# connectors.net
KiCad netlist of a schematic drawn in Altium Designer
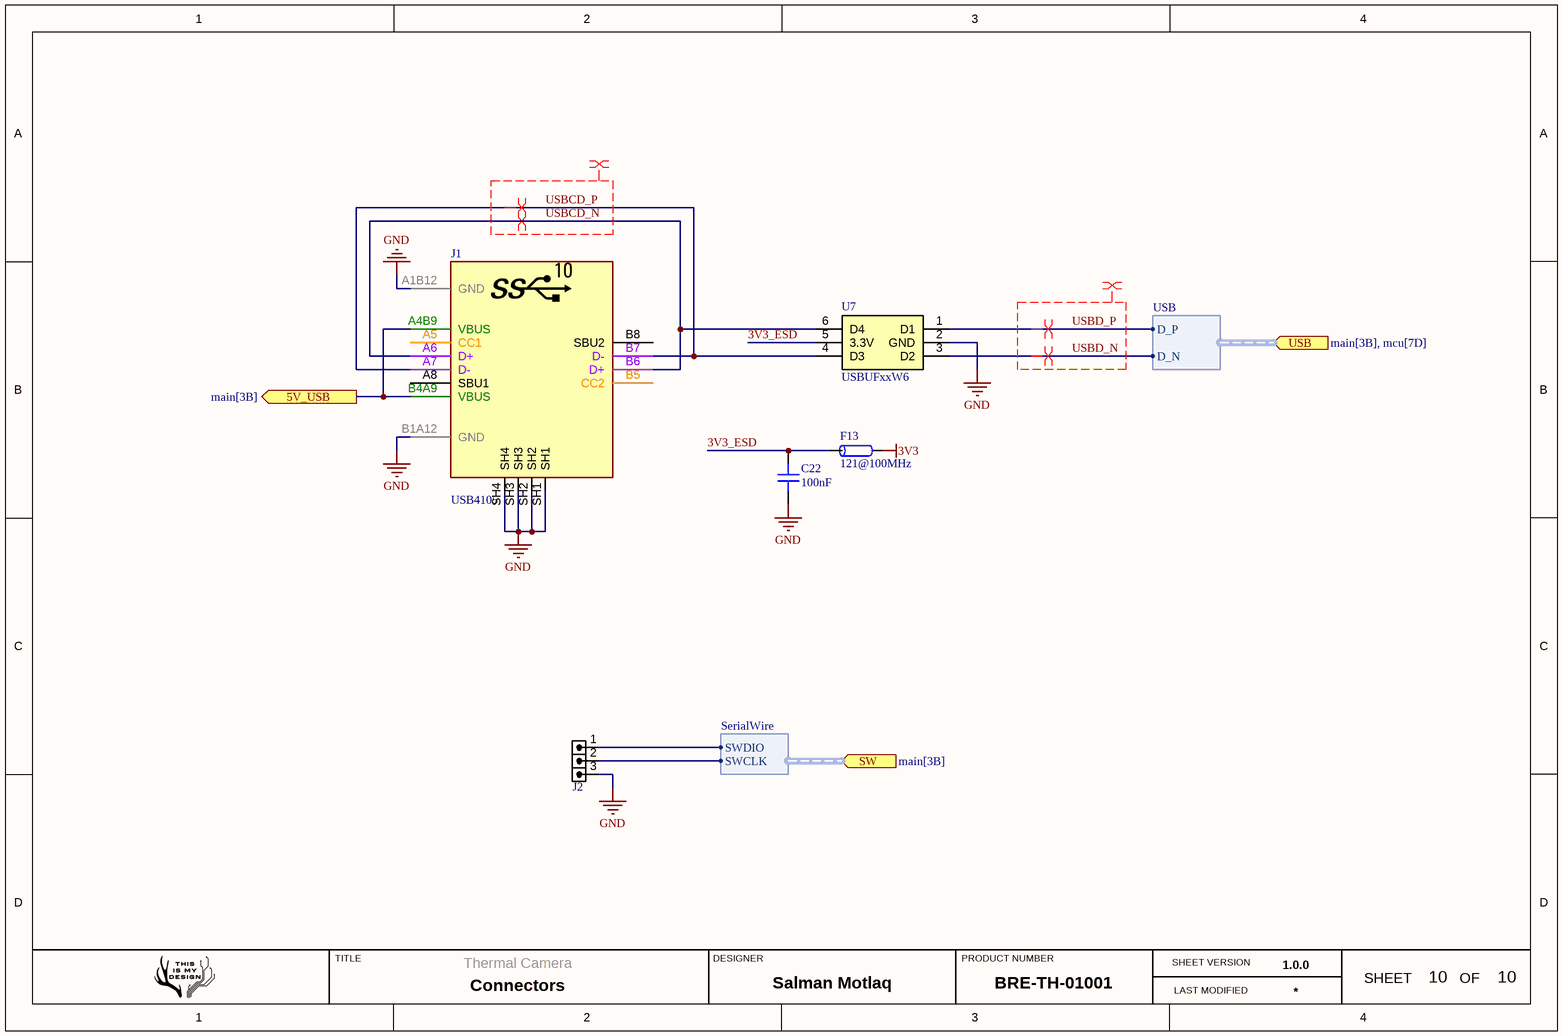
[diagram p0: connectors.SchDoc]

(export (version "E")
  (design (tool "Eeschema 10.0.6"))
  (components
    (comp (ref "C22")
      (value "100nF")
      (footprint "CAP 0603_1608")
      (description "SMT Capacitor")
      (libsource (lib "Capacitor") (part "Cap 0603"))
    )
    (comp (ref "F13")
      (value "121@100MHz")
      (footprint "Ferrite-0805")
      (description "Ferrite Bead")
      (libsource (lib "Salman_lib") (part "Ferrite Bead"))
    )
    (comp (ref "J1")
      (value "USB4105")
      (footprint "USBC_SMD_16_USB4105")
      (description "CONN, USB, Type C, USB 2.0, Right-Angle, SMD")
      (fields (field (name "MANF") "GCT") (field (name "MANF_P#") "USB4105-GF-A"))
      (libsource (lib "Salman_lib") (part "CONN_USBC_SMD_16_USB4105"))
    )
    (comp (ref "J2")
      (value "HDRM3")
      (footprint "HDRR_M_1X3")
      (description "CONN, HEADER, RightAngle, Male, pitch: 2.54mm, 3POS")
      (libsource (lib "Conn Header") (part "HDRR_M_1X3"))
    )
    (comp (ref "U7")
      (value "USBUFxxW6")
      (footprint "SOT23-6L")
      (description "USBUF02W6")
      (libsource (lib "Salman_lib") (part "USBUFxxW6"))
    )
  )
  (nets
    (net (code "3") (name "/3V3_ESD") (class "Default")
      (node (ref "C22") (pin "2") (pinfunction "2_2") (pintype "passive"))
      (node (ref "F13") (pin "2") (pinfunction "66_2") (pintype "passive"))
      (node (ref "U7") (pin "5") (pinfunction "3.3V_5") (pintype "passive"))
    )
    (net (code "4") (name "/5V_USB") (class "Default")
      (node (ref "J1") (pin "A4B9") (pinfunction "VBUS_A4B9") (pintype "passive"))
      (node (ref "J1") (pin "B4A9") (pinfunction "VBUS_B4A9") (pintype "passive"))
    )
    (net (code "5") (name "/SWCLK") (class "Default")
      (node (ref "J2") (pin "2") (pinfunction "2_2") (pintype "passive"))
    )
    (net (code "6") (name "/SWDIO") (class "Default")
      (node (ref "J2") (pin "1") (pinfunction "1_1") (pintype "passive"))
    )
    (net (code "7") (name "/USBCD_N") (class "Default")
      (node (ref "J1") (pin "A6") (pinfunction "D+_A6") (pintype "passive"))
      (node (ref "J1") (pin "B6") (pinfunction "D+_B6") (pintype "passive"))
      (node (ref "U7") (pin "6") (pinfunction "D4_6") (pintype "passive"))
    )
    (net (code "8") (name "/USBCD_P") (class "Default")
      (node (ref "J1") (pin "A7") (pinfunction "D-_A7") (pintype "passive"))
      (node (ref "J1") (pin "B7") (pinfunction "D-_B7") (pintype "passive"))
      (node (ref "U7") (pin "4") (pinfunction "D3_4") (pintype "passive"))
    )
    (net (code "9") (name "/USBD_N") (class "Default")
      (node (ref "U7") (pin "3") (pinfunction "D2_3") (pintype "passive"))
    )
    (net (code "10") (name "/USBD_P") (class "Default")
      (node (ref "U7") (pin "1") (pinfunction "D1_1") (pintype "passive"))
    )
    (net (code "13") (name "3V3") (class "Default")
      (node (ref "F13") (pin "1") (pinfunction "67_1") (pintype "passive"))
    )
    (net (code "14") (name "GND") (class "Default")
      (node (ref "C22") (pin "1") (pinfunction "1_1") (pintype "passive"))
      (node (ref "J1") (pin "A1B12") (pinfunction "GND_A1B12") (pintype "passive"))
      (node (ref "J1") (pin "B1A12") (pinfunction "GND_B1A12") (pintype "passive"))
      (node (ref "J1") (pin "SH1") (pinfunction "SH1_SH1") (pintype "passive"))
      (node (ref "J1") (pin "SH2") (pinfunction "SH2_SH2") (pintype "passive"))
      (node (ref "J1") (pin "SH3") (pinfunction "SH3_SH3") (pintype "passive"))
      (node (ref "J1") (pin "SH4") (pinfunction "SH4_SH4") (pintype "passive"))
      (node (ref "J2") (pin "3") (pinfunction "3_3") (pintype "passive"))
      (node (ref "U7") (pin "2") (pinfunction "GND_2") (pintype "passive"))
    )
    (net (code "15") (name "unconnected-(J1-CC1-PadA5)") (class "Default")
      (node (ref "J1") (pin "A5") (pinfunction "CC1_A5") (pintype "passive"))
    )
    (net (code "16") (name "unconnected-(J1-CC2-PadB5)") (class "Default")
      (node (ref "J1") (pin "B5") (pinfunction "CC2_B5") (pintype "passive"))
    )
    (net (code "17") (name "unconnected-(J1-SBU1-PadA8)") (class "Default")
      (node (ref "J1") (pin "A8") (pinfunction "SBU1_A8") (pintype "passive"))
    )
    (net (code "18") (name "unconnected-(J1-SBU2-PadB8)") (class "Default")
      (node (ref "J1") (pin "B8") (pinfunction "SBU2_B8") (pintype "passive"))
    )
  )
)
